# 5V_Buck_Boost_Converter.net
KiCad netlist of a schematic drawn in Altium Designer
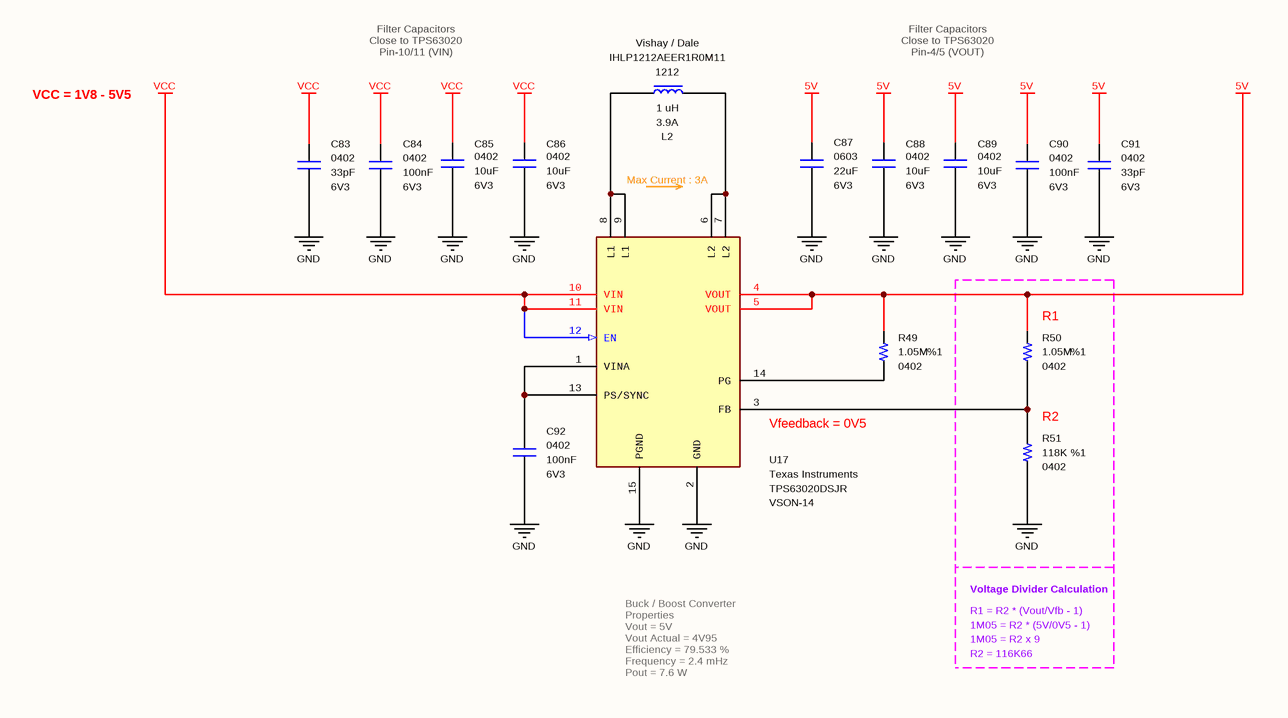
[diagram p0: 5V Buck Boost Converter.SchDoc]

(export (version "E")
  (design (tool "Eeschema 10.0.6"))
  (components
    (comp (ref "C83")
      (value "33pF")
      (footprint "CAPACITOR_0402")
      (description "Capacitor - 33pF [0402] (Ceramic)")
      (fields
        (field (name "TOLERANCE") "10%")
        (field (name "CASE") "0402")
        (field (name "VOLTAGE") "6V3")
        (field (name "MANUFACTURER PART NUMBER") "C0402C330J9RACAUTO")
      )
      (libsource (lib "Ovoo_Library") (part "Capacitor - 33pF [0402-6V3]"))
    )
    (comp (ref "C84")
      (value "100nF")
      (footprint "CAPACITOR_0402")
      (description "Capacitor - 100nF [0402-6V3] (Ceramic)")
      (fields
        (field (name "CASE") "0402")
        (field (name "TOLERANCE") "%10")
        (field (name "VOLTAGE") "6V3")
        (field (name "MANUFACTURER PART NUMBER") "04026D104KAT4A")
      )
      (libsource (lib "Ovoo_Library") (part "Capacitor - 100nF [0402-6V3]"))
    )
    (comp (ref "C85")
      (value "10uF")
      (footprint "CAPACITOR_0402")
      (description "Capacitor - 10uF [0402] (Ceramic)")
      (fields
        (field (name "MANUFACTURER PART NUMBER") "C0402C106M9PACTU")
        (field (name "MOUSER PART NUMBER") "80-C0402C106M9P")
        (field (name "CASE") "0402")
        (field (name "VOLTAGE") "6V3")
      )
      (libsource (lib "Ovoo_Library") (part "Capacitor - 10uF [0402-6V3]"))
    )
    (comp (ref "C86")
      (value "10uF")
      (footprint "CAPACITOR_0402")
      (description "Capacitor - 10uF [0402] (Ceramic)")
      (fields
        (field (name "MANUFACTURER PART NUMBER") "C0402C106M9PACTU")
        (field (name "MOUSER PART NUMBER") "80-C0402C106M9P")
        (field (name "CASE") "0402")
        (field (name "VOLTAGE") "6V3")
      )
      (libsource (lib "Ovoo_Library") (part "Capacitor - 10uF [0402-6V3]"))
    )
    (comp (ref "C87")
      (value "22uF")
      (footprint "CAPACITOR_0603")
      (description "Capacitor - 22uF [0603] (Ceramic)")
      (fields
        (field (name "MANUFACTURER PART NUMBER") "GRM188R60J226MEA0D")
        (field (name "TOLERANCE") "%20")
        (field (name "CASE") "0603")
        (field (name "VOLTAGE") "6V3")
      )
      (libsource (lib "Ovoo_Library") (part "Capacitor - 22uF [0603-6V3]"))
    )
    (comp (ref "C88")
      (value "10uF")
      (footprint "CAPACITOR_0402")
      (description "Capacitor - 10uF [0402] (Ceramic)")
      (fields
        (field (name "MANUFACTURER PART NUMBER") "C0402C106M9PACTU")
        (field (name "MOUSER PART NUMBER") "80-C0402C106M9P")
        (field (name "CASE") "0402")
        (field (name "VOLTAGE") "6V3")
      )
      (libsource (lib "Ovoo_Library") (part "Capacitor - 10uF [0402-6V3]"))
    )
    (comp (ref "C89")
      (value "10uF")
      (footprint "CAPACITOR_0402")
      (description "Capacitor - 10uF [0402] (Ceramic)")
      (fields
        (field (name "MANUFACTURER PART NUMBER") "C0402C106M9PACTU")
        (field (name "MOUSER PART NUMBER") "80-C0402C106M9P")
        (field (name "CASE") "0402")
        (field (name "VOLTAGE") "6V3")
      )
      (libsource (lib "Ovoo_Library") (part "Capacitor - 10uF [0402-6V3]"))
    )
    (comp (ref "C90")
      (value "100nF")
      (footprint "CAPACITOR_0402")
      (description "Capacitor - 100nF [0402-6V3] (Ceramic)")
      (fields
        (field (name "CASE") "0402")
        (field (name "TOLERANCE") "%10")
        (field (name "VOLTAGE") "6V3")
        (field (name "MANUFACTURER PART NUMBER") "04026D104KAT4A")
      )
      (libsource (lib "Ovoo_Library") (part "Capacitor - 100nF [0402-6V3]"))
    )
    (comp (ref "C91")
      (value "33pF")
      (footprint "CAPACITOR_0402")
      (description "Capacitor - 33pF [0402] (Ceramic)")
      (fields
        (field (name "TOLERANCE") "10%")
        (field (name "CASE") "0402")
        (field (name "VOLTAGE") "6V3")
        (field (name "MANUFACTURER PART NUMBER") "C0402C330J9RACAUTO")
      )
      (libsource (lib "Ovoo_Library") (part "Capacitor - 33pF [0402-6V3]"))
    )
    (comp (ref "C92")
      (value "100nF")
      (footprint "CAPACITOR_0402")
      (description "Capacitor - 100nF [0402-6V3] (Ceramic)")
      (fields
        (field (name "CASE") "0402")
        (field (name "TOLERANCE") "%10")
        (field (name "VOLTAGE") "6V3")
        (field (name "MANUFACTURER PART NUMBER") "04026D104KAT4A")
      )
      (libsource (lib "Ovoo_Library") (part "Capacitor - 100nF [0402-6V3]"))
    )
    (comp (ref "L2")
      (value "1 uH")
      (footprint "IHLP-1212")
      (description "Fixed Inductors 1uH 20%")
      (fields
        (field (name "TOLERANCE") "20%")
        (field (name "MAXIMUM DC CURRENT") "3.9A")
        (field (name "CASE") "1212")
        (field (name "MANUFACTURER PART NUMBER") "IHLP1212AEER1R0M11")
        (field (name "MANUFACTURER NAME") "Vishay / Dale")
        (field (name "Comment") "Vishay - IHLP1212AEER1R0M11")
      )
      (libsource (lib "Ovoo_Library") (part "Inductor - 1 uH [1212]"))
    )
    (comp (ref "R49")
      (value "1.05M")
      (footprint "RESISTOR_0402")
      (description "Thick Film Resistors - SMD 1/16 W 1.05 Mohms 1%")
      (fields
        (field (name "MANUFACTURER PART NUMBER") "CRCW04021M05FKED")
        (field (name "MOUSER PART NUMBER") "71-CRCW04021M05FKED")
        (field (name "TOLERANCE") "%1")
        (field (name "CASE") "0402")
      )
      (libsource (lib "Ovoo_Library") (part "Resistor - 1.05M"))
    )
    (comp (ref "R50")
      (value "1.05M")
      (footprint "RESISTOR_0402")
      (description "Thick Film Resistors - SMD 1/16 W 1.05 Mohms 1%")
      (fields
        (field (name "MANUFACTURER PART NUMBER") "CRCW04021M05FKED")
        (field (name "MOUSER PART NUMBER") "71-CRCW04021M05FKED")
        (field (name "TOLERANCE") "%1")
        (field (name "CASE") "0402")
      )
      (libsource (lib "Ovoo_Library") (part "Resistor - 1.05M"))
    )
    (comp (ref "R51")
      (value "118K")
      (footprint "RESISTOR_0402")
      (description "Thick Film Resistors - SMD 1/16 W 118 Kohms 1%")
      (fields
        (field (name "MANUFACTURER PART NUMBER") "CRCW0402118KFKED")
        (field (name "TOLERANCE") "%1")
        (field (name "CASE") "0402")
        (field (name "Comment") "Thick Film Resistor")
      )
      (libsource (lib "Schematic") (part "Resistor - 118K"))
    )
    (comp (ref "U17")
      (value "Texas Instruments - TPS63020DSJR")
      (footprint "VSON-14")
      (description "Switching Voltage Regulators 93% Eff Buck-Boost Converter")
      (fields
        (field (name "MANUFACTURER PART NUMBER") "TPS63020DSJR")
        (field (name "MANUFACTURER NAME") "Texas Instruments")
        (field (name "CASE") "VSON-14")
      )
      (libsource (lib "Ovoo_Library") (part "IC - TPS63020DSJR"))
    )
  )
  (nets
    (net (code "1") (name "5V") (class "Default")
      (node (ref "C87") (pin "2") (pinfunction "2_2") (pintype "passive"))
      (node (ref "C88") (pin "2") (pinfunction "2_2") (pintype "passive"))
      (node (ref "C89") (pin "2") (pinfunction "2_2") (pintype "passive"))
      (node (ref "C90") (pin "1") (pinfunction "1_1") (pintype "passive"))
      (node (ref "C91") (pin "2") (pinfunction "2_2") (pintype "passive"))
      (node (ref "R49") (pin "2") (pinfunction "2_2") (pintype "passive"))
      (node (ref "R50") (pin "2") (pinfunction "2_2") (pintype "passive"))
      (node (ref "U17") (pin "4") (pinfunction "VOUT_4") (pintype "power_in"))
      (node (ref "U17") (pin "5") (pinfunction "VOUT_5") (pintype "power_in"))
    )
    (net (code "2") (name "GND") (class "Default")
      (node (ref "C83") (pin "1") (pinfunction "1_1") (pintype "passive"))
      (node (ref "C84") (pin "2") (pinfunction "2_2") (pintype "passive"))
      (node (ref "C85") (pin "1") (pinfunction "1_1") (pintype "passive"))
      (node (ref "C86") (pin "1") (pinfunction "1_1") (pintype "passive"))
      (node (ref "C87") (pin "1") (pinfunction "1_1") (pintype "passive"))
      (node (ref "C88") (pin "1") (pinfunction "1_1") (pintype "passive"))
      (node (ref "C89") (pin "1") (pinfunction "1_1") (pintype "passive"))
      (node (ref "C90") (pin "2") (pinfunction "2_2") (pintype "passive"))
      (node (ref "C91") (pin "1") (pinfunction "1_1") (pintype "passive"))
      (node (ref "C92") (pin "2") (pinfunction "2_2") (pintype "passive"))
      (node (ref "R51") (pin "1") (pinfunction "1_1") (pintype "passive"))
      (node (ref "U17") (pin "15") (pinfunction "PGND_15") (pintype "power_in"))
      (node (ref "U17") (pin "2") (pinfunction "GND_2") (pintype "power_in"))
    )
    (net (code "3") (name "Net-(L2-Pad1)") (class "Default")
      (node (ref "L2") (pin "1") (pinfunction "1_1") (pintype "passive"))
      (node (ref "U17") (pin "8") (pinfunction "L1_8") (pintype "passive"))
      (node (ref "U17") (pin "9") (pinfunction "L1_9") (pintype "passive"))
    )
    (net (code "4") (name "Net-(L2-Pad2)") (class "Default")
      (node (ref "L2") (pin "2") (pinfunction "2_2") (pintype "passive"))
      (node (ref "U17") (pin "6") (pinfunction "L2_6") (pintype "passive"))
      (node (ref "U17") (pin "7") (pinfunction "L2_7") (pintype "passive"))
    )
    (net (code "5") (name "Net-(U17-FB)") (class "Default")
      (node (ref "R50") (pin "1") (pinfunction "1_1") (pintype "passive"))
      (node (ref "R51") (pin "2") (pinfunction "2_2") (pintype "passive"))
      (node (ref "U17") (pin "3") (pinfunction "FB_3") (pintype "passive"))
    )
    (net (code "6") (name "Net-(U17-PG)") (class "Default")
      (node (ref "R49") (pin "1") (pinfunction "1_1") (pintype "passive"))
      (node (ref "U17") (pin "14") (pinfunction "PG_14") (pintype "passive"))
    )
    (net (code "7") (name "Net-(U17-PS{slash}SYNC)") (class "Default")
      (node (ref "C92") (pin "1") (pinfunction "1_1") (pintype "passive"))
      (node (ref "U17") (pin "1") (pinfunction "VINA_1") (pintype "passive"))
      (node (ref "U17") (pin "13") (pinfunction "PS/SYNC_13") (pintype "passive"))
    )
    (net (code "8") (name "VCC") (class "Default")
      (node (ref "C83") (pin "2") (pinfunction "2_2") (pintype "passive"))
      (node (ref "C84") (pin "1") (pinfunction "1_1") (pintype "passive"))
      (node (ref "C85") (pin "2") (pinfunction "2_2") (pintype "passive"))
      (node (ref "C86") (pin "2") (pinfunction "2_2") (pintype "passive"))
      (node (ref "U17") (pin "10") (pinfunction "VIN_10") (pintype "power_in"))
      (node (ref "U17") (pin "11") (pinfunction "VIN_11") (pintype "power_in"))
      (node (ref "U17") (pin "12") (pinfunction "EN_12") (pintype "input"))
    )
  )
)
